# untitled.net
KiCad netlist of a schematic drawn in EAGLE
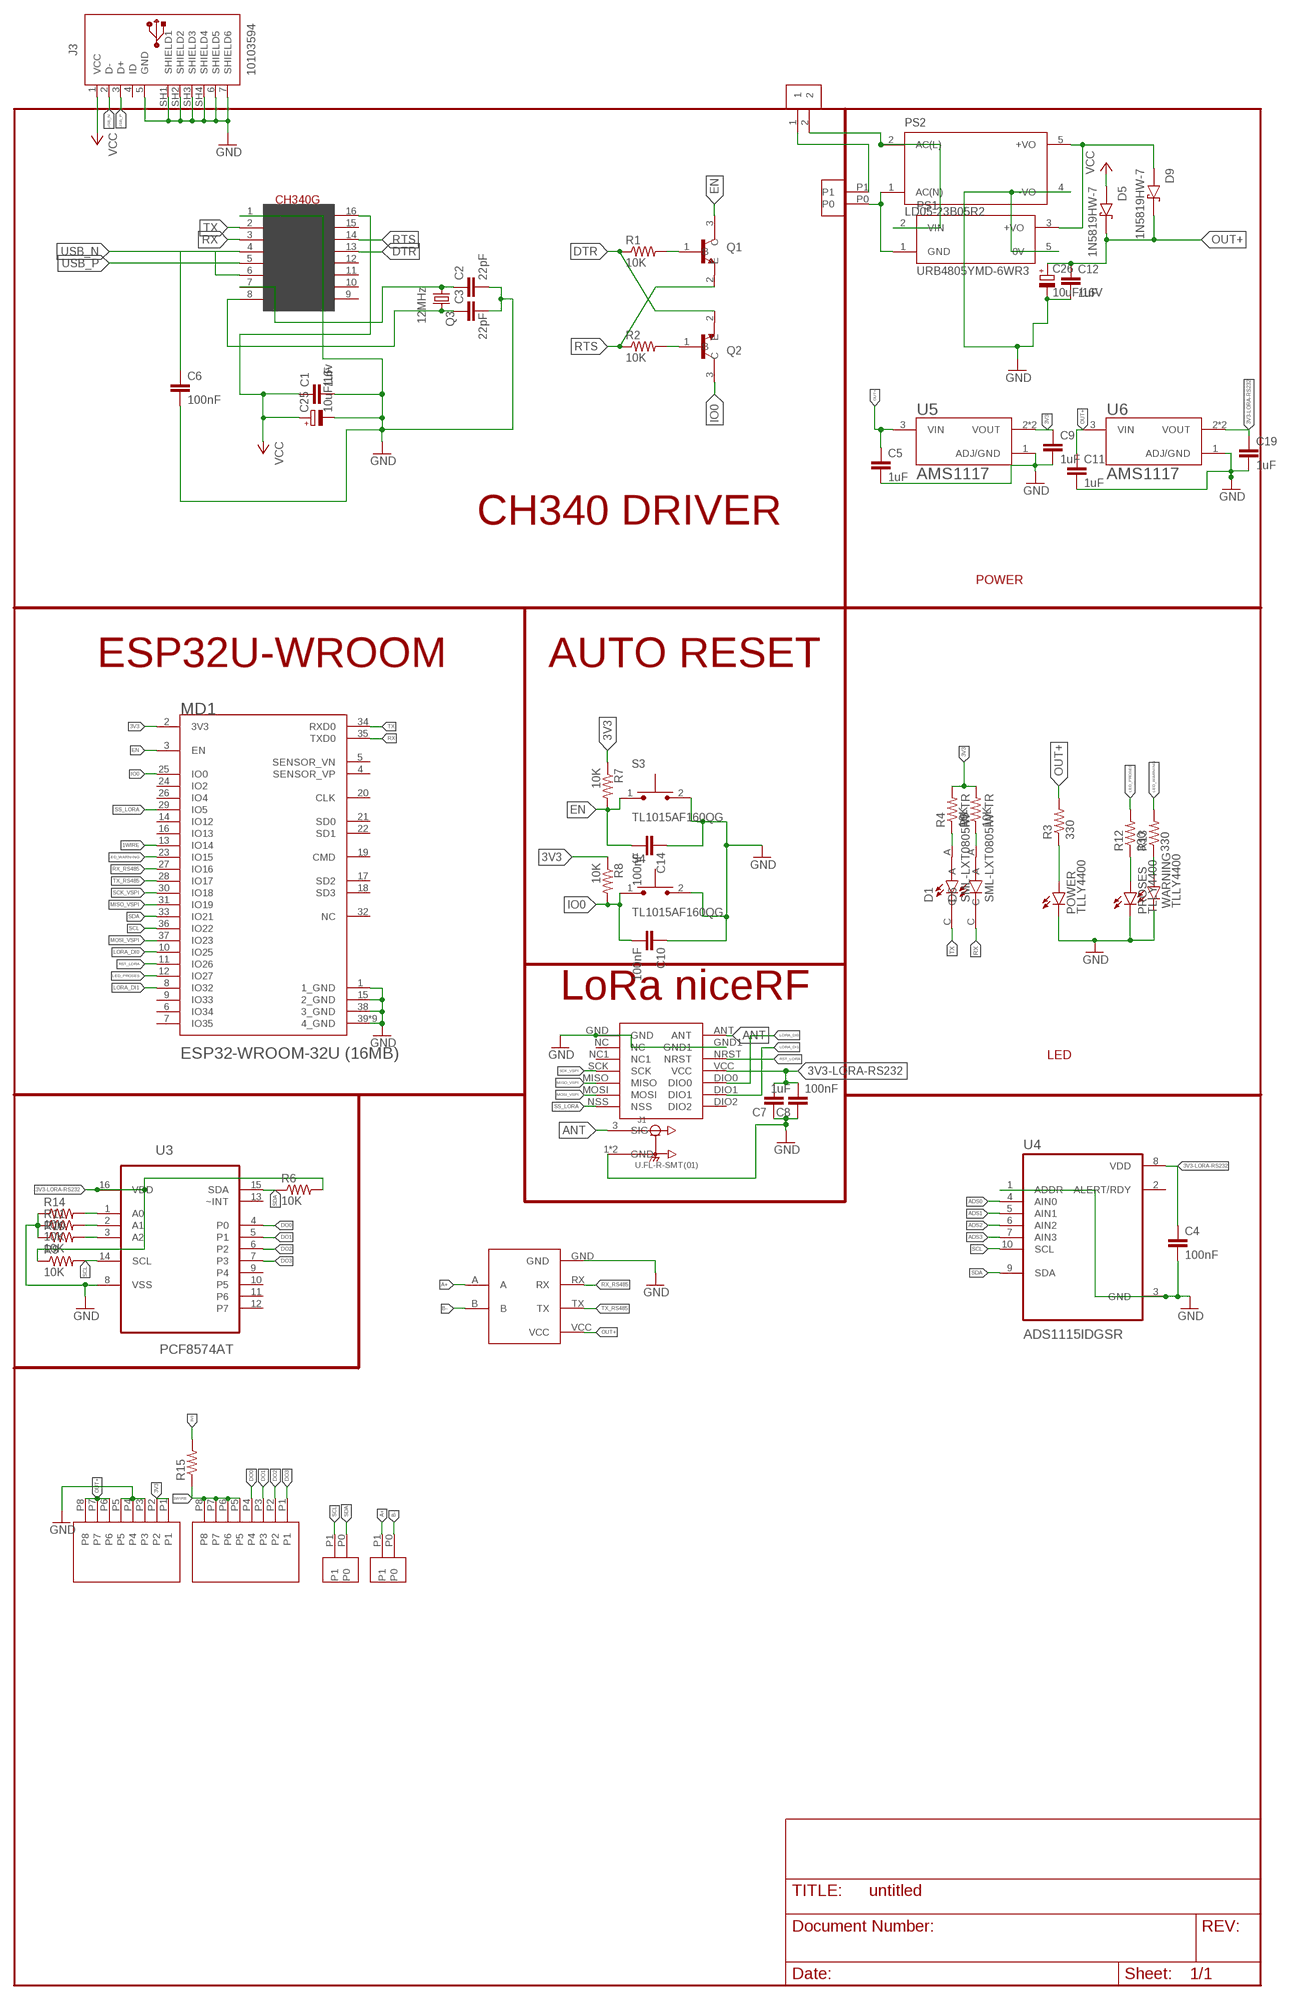
[diagram p0: schematic, sheet 1]

(export (version "E")
  (design (tool "Eeschema 10.0.6"))
  (components
    (comp (ref "C1")
      (value "1uF")
      (footprint "eagle-import:C0805K")
      (libsource (lib "eagle-import") (part "C-EUC0805K"))
    )
    (comp (ref "C2")
      (value "22pF")
      (footprint "eagle-import:C0805K")
      (libsource (lib "eagle-import") (part "C-EUC0805K"))
    )
    (comp (ref "C3")
      (value "22pF")
      (footprint "eagle-import:C0805K")
      (libsource (lib "eagle-import") (part "C-EUC0805K"))
    )
    (comp (ref "C4")
      (value "100nF")
      (footprint "eagle-import:C0805K")
      (libsource (lib "eagle-import") (part "C-EUC0805K"))
    )
    (comp (ref "C5")
      (value "1uF")
      (footprint "eagle-import:C0805K")
      (libsource (lib "eagle-import") (part "C-EUC0805K"))
    )
    (comp (ref "C6")
      (value "100nF")
      (footprint "eagle-import:C0805K")
      (libsource (lib "eagle-import") (part "C-EUC0805K"))
    )
    (comp (ref "C7")
      (value "1uF")
      (footprint "eagle-import:C0805K")
      (libsource (lib "eagle-import") (part "C-EUC0805K"))
    )
    (comp (ref "C8")
      (value "100nF")
      (footprint "eagle-import:C0805K")
      (libsource (lib "eagle-import") (part "C-EUC0805K"))
    )
    (comp (ref "C9")
      (value "1uF")
      (footprint "eagle-import:C0805K")
      (libsource (lib "eagle-import") (part "C-EUC0805K"))
    )
    (comp (ref "C10")
      (value "100nF")
      (footprint "eagle-import:C0805K")
      (libsource (lib "eagle-import") (part "C-EUC0805K"))
    )
    (comp (ref "C11")
      (value "1uF")
      (footprint "eagle-import:C0805K")
      (libsource (lib "eagle-import") (part "C-EUC0805K"))
    )
    (comp (ref "C12")
      (value "1uF")
      (footprint "eagle-import:C0805K")
      (libsource (lib "eagle-import") (part "C-EUC0805K"))
    )
    (comp (ref "C14")
      (value "100nF")
      (footprint "eagle-import:C0805K")
      (libsource (lib "eagle-import") (part "C-EUC0805K"))
    )
    (comp (ref "C19")
      (value "1uF")
      (footprint "eagle-import:C0805K")
      (libsource (lib "eagle-import") (part "C-EUC0805K"))
    )
    (comp (ref "C25")
      (value "10uF/16v")
      (footprint "eagle-import:153CLV-0505")
      (libsource (lib "eagle-import") (part "CPOL-EU153CLV-0505"))
    )
    (comp (ref "C26")
      (value "10uF/16V")
      (footprint "eagle-import:153CLV-0505")
      (libsource (lib "eagle-import") (part "CPOL-EU153CLV-0505"))
    )
    (comp (ref "CONN2P-3.5PI1")
      (value "CONN2P-3.5PI")
      (footprint "eagle-import:CONN2P-3.5PI")
      (libsource (lib "eagle-import") (part "CONN2P-3.5PI"))
    )
    (comp (ref "CONN2P-3.5PI2")
      (value "CONN2P-3.5PI")
      (footprint "eagle-import:CONN2P-3.5PI")
      (libsource (lib "eagle-import") (part "CONN2P-3.5PI"))
    )
    (comp (ref "CONN2P-3.5PI3")
      (value "CONN2P-3.5PI")
      (footprint "eagle-import:CONN2P-3.5PI")
      (libsource (lib "eagle-import") (part "CONN2P-3.5PI"))
    )
    (comp (ref "CONN3.1")
      (value "CONN3.5")
      (footprint "eagle-import:CONN3.5")
      (libsource (lib "eagle-import") (part "CONN3.5"))
    )
    (comp (ref "CONN3.2")
      (value "CONN3.5")
      (footprint "eagle-import:CONN3.5")
      (libsource (lib "eagle-import") (part "CONN3.5"))
    )
    (comp (ref "D1")
      (value "SML-LXT0805IW-TR")
      (footprint "eagle-import:LEDC2012X120N")
      (fields (field (name "MF") "Lumex Opto/Components"))
      (libsource (lib "eagle-import") (part "SML-LXT0805IW-TR"))
    )
    (comp (ref "D5")
      (value "1N5819HW-7")
      (footprint "eagle-import:SOD3715X145N")
      (fields (field (name "MF") "Diodes Inc."))
      (libsource (lib "eagle-import") (part "1N5819HW-7"))
    )
    (comp (ref "D6")
      (value "SML-LXT0805IW-TR")
      (footprint "eagle-import:LEDC2012X120N")
      (fields (field (name "MF") "Lumex Opto/Components"))
      (libsource (lib "eagle-import") (part "SML-LXT0805IW-TR"))
    )
    (comp (ref "D9")
      (value "1N5819HW-7")
      (footprint "eagle-import:SOD3715X145N")
      (fields (field (name "MF") "Diodes Inc."))
      (libsource (lib "eagle-import") (part "1N5819HW-7"))
    )
    (comp (ref "FUSE-KOTAK1")
      (value "FUSE-KOTAK")
      (footprint "eagle-import:FUSE-KOTAK")
      (libsource (lib "eagle-import") (part "FUSE-KOTAK"))
    )
    (comp (ref "J1")
      (value "U.FL-R-SMT(01)")
      (footprint "eagle-import:HRS_U.FL-R-SMT(01)")
      (fields (field (name "MF") "Hirose"))
      (libsource (lib "eagle-import") (part "U.FL-R-SMT(01)"))
    )
    (comp (ref "J3")
      (value "10103594")
      (footprint "eagle-import:10103594")
      (fields (field (name "MANUFACTURER") "Amphenol ICC (FCI)") (field (name "MPN") "10103594-0001LF"))
      (libsource (lib "eagle-import") (part "10103594"))
    )
    (comp (ref "LORA-NICERF-V1")
      (value "LORA-NICERF-V2")
      (footprint "eagle-import:LORA-NICERF-V2")
      (libsource (lib "eagle-import") (part "LORA-NICERF-V2"))
    )
    (comp (ref "MD1")
      (value "ESPRESSIF_SYSTEMS_ESP32-WROOM-32U_16MBESPRESSIF_SYSTEMS_ESP32-WROOM-32U_16MB_0_0")
      (footprint "eagle-import:ESPRESSIF_SYSTEMS_ESP32-WROOM-32U_16MB_0")
      (fields
        (field (name "DIGIKEY_PART_NUMBER") "1904-1028-1-ND")
        (field (name "MF") "Espressif Systems")
        (field (name "MOUSER_PART_NUMBER") "356-ES32WROOM32U16MB")
      )
      (libsource (lib "eagle-import") (part "ESPRESSIF_SYSTEMS_ESP32-WROOM-32U_16MBESPRESSIF_SYSTEMS_ESP32-WROOM-32U_16MB_0_0"))
    )
    (comp (ref "POWER")
      (value "TLLY4400")
      (footprint "eagle-import:LED3MM")
      (fields (field (name "MF") "VISHAY SEMICONDUCTOR"))
      (libsource (lib "eagle-import") (part "TLLY4400"))
    )
    (comp (ref "PROSES")
      (value "TLLY4400")
      (footprint "eagle-import:LED3MM")
      (fields (field (name "MF") "VISHAY SEMICONDUCTOR"))
      (libsource (lib "eagle-import") (part "TLLY4400"))
    )
    (comp (ref "PS1")
      (value "URB4805YMD-6WR3")
      (footprint "eagle-import:CONV_URB4805YMD-6WR3")
      (fields (field (name "MF") "Mornsun America, LLC"))
      (libsource (lib "eagle-import") (part "URB4805YMD-6WR3"))
    )
    (comp (ref "PS2")
      (value "LD05-23B05R2")
      (footprint "eagle-import:CONV_LD05-23B05R2")
      (fields (field (name "MF") "Mornsun America, LLC"))
      (libsource (lib "eagle-import") (part "LD05-23B05R2"))
    )
    (comp (ref "Q1")
      (value "MMBT3904")
      (footprint "eagle-import:SOT95P240X120-3N")
      (fields (field (name "MF") "STMicroelectronics"))
      (libsource (lib "eagle-import") (part "MMBT3904"))
    )
    (comp (ref "Q2")
      (value "MMBT3904")
      (footprint "eagle-import:SOT95P240X120-3N")
      (fields (field (name "MF") "STMicroelectronics"))
      (libsource (lib "eagle-import") (part "MMBT3904"))
    )
    (comp (ref "Q3")
      (value "12MHz")
      (footprint "eagle-import:SM49")
      (libsource (lib "eagle-import") (part "CRYSTALSM49"))
    )
    (comp (ref "R1")
      (value "10K")
      (footprint "eagle-import:M0805")
      (libsource (lib "eagle-import") (part "R-US_M0805"))
    )
    (comp (ref "R2")
      (value "10K")
      (footprint "eagle-import:M0805")
      (libsource (lib "eagle-import") (part "R-US_M0805"))
    )
    (comp (ref "R3")
      (value "330")
      (footprint "eagle-import:M0805")
      (libsource (lib "eagle-import") (part "R-US_M0805"))
    )
    (comp (ref "R4")
      (value "10K")
      (footprint "eagle-import:M0805")
      (libsource (lib "eagle-import") (part "R-US_M0805"))
    )
    (comp (ref "R5")
      (value "10K")
      (footprint "eagle-import:M0805")
      (libsource (lib "eagle-import") (part "R-US_M0805"))
    )
    (comp (ref "R6")
      (value "10K")
      (footprint "eagle-import:M0805")
      (libsource (lib "eagle-import") (part "R-US_M0805"))
    )
    (comp (ref "R7")
      (value "10K")
      (footprint "eagle-import:M0805")
      (libsource (lib "eagle-import") (part "R-US_M0805"))
    )
    (comp (ref "R8")
      (value "10K")
      (footprint "eagle-import:M0805")
      (libsource (lib "eagle-import") (part "R-US_M0805"))
    )
    (comp (ref "R9")
      (value "10K")
      (footprint "eagle-import:M0805")
      (libsource (lib "eagle-import") (part "R-US_M0805"))
    )
    (comp (ref "R10")
      (value "10K")
      (footprint "eagle-import:M0805")
      (libsource (lib "eagle-import") (part "R-US_M0805"))
    )
    (comp (ref "R11")
      (value "10K")
      (footprint "eagle-import:M0805")
      (libsource (lib "eagle-import") (part "R-US_M0805"))
    )
    (comp (ref "R12")
      (value "330")
      (footprint "eagle-import:M0805")
      (libsource (lib "eagle-import") (part "R-US_M0805"))
    )
    (comp (ref "R13")
      (value "330")
      (footprint "eagle-import:M0805")
      (libsource (lib "eagle-import") (part "R-US_M0805"))
    )
    (comp (ref "R14")
      (value "10K")
      (footprint "eagle-import:M0805")
      (libsource (lib "eagle-import") (part "R-US_M0805"))
    )
    (comp (ref "R15")
      (value "R-US_0207/10")
      (footprint "eagle-import:0207_10")
      (libsource (lib "eagle-import") (part "R-US_0207/10"))
    )
    (comp (ref "S3")
      (value "TL1015AF160QG")
      (footprint "eagle-import:SW_TL1015AF160QG")
      (fields (field (name "MF") "E-Switch"))
      (libsource (lib "eagle-import") (part "TL1015AF160QG"))
    )
    (comp (ref "S4")
      (value "TL1015AF160QG")
      (footprint "eagle-import:SW_TL1015AF160QG")
      (fields (field (name "MF") "E-Switch"))
      (libsource (lib "eagle-import") (part "TL1015AF160QG"))
    )
    (comp (ref "TTL-RS1")
      (value "TTL-RS485")
      (footprint "eagle-import:TTL-RS485")
      (libsource (lib "eagle-import") (part "TTL-RS485"))
    )
    (comp (ref "U$2")
      (value "CH340G")
      (footprint "eagle-import:SOIC16")
      (libsource (lib "eagle-import") (part "CH340G"))
    )
    (comp (ref "U3")
      (value "PCF8574AT")
      (footprint "eagle-import:SOIC127P1032X265-16N")
      (fields (field (name "MF") "NXP USA"))
      (libsource (lib "eagle-import") (part "PCF8574AT"))
    )
    (comp (ref "U4")
      (value "ADS1115IDGSR")
      (footprint "eagle-import:SOP50P490X110-10N")
      (fields (field (name "MF") "Texas Instruments"))
      (libsource (lib "eagle-import") (part "ADS1115IDGSR"))
    )
    (comp (ref "U5")
      (value "AMS1117")
      (footprint "eagle-import:SOT229P700X180-4N")
      (fields (field (name "MF") "Advanced Monolithic Systems"))
      (libsource (lib "eagle-import") (part "AMS1117"))
    )
    (comp (ref "U6")
      (value "AMS1117")
      (footprint "eagle-import:SOT229P700X180-4N")
      (fields (field (name "MF") "Advanced Monolithic Systems"))
      (libsource (lib "eagle-import") (part "AMS1117"))
    )
    (comp (ref "WARNING")
      (value "TLLY4400")
      (footprint "eagle-import:LED3MM")
      (fields (field (name "MF") "VISHAY SEMICONDUCTOR"))
      (libsource (lib "eagle-import") (part "TLLY4400"))
    )
  )
  (nets
    (net (code "1") (name "1WIRE") (class "Default")
      (node (ref "CONN3.2") (pin "P5") (pinfunction "P5_P5") (pintype "bidirectional"))
      (node (ref "CONN3.2") (pin "P6") (pinfunction "P6_P6") (pintype "bidirectional"))
      (node (ref "CONN3.2") (pin "P7") (pinfunction "P7_P7") (pintype "bidirectional"))
      (node (ref "CONN3.2") (pin "P8") (pinfunction "P8_P8") (pintype "bidirectional"))
      (node (ref "MD1") (pin "13") (pinfunction "IO14_13") (pintype "bidirectional"))
      (node (ref "R15") (pin "1") (pinfunction "1_1") (pintype "passive"))
    )
    (net (code "2") (name "3V3") (class "Default")
      (node (ref "C9") (pin "1") (pinfunction "1_1") (pintype "passive"))
      (node (ref "CONN3.1") (pin "P1") (pinfunction "P1_P1") (pintype "bidirectional"))
      (node (ref "CONN3.1") (pin "P2") (pinfunction "P2_P2") (pintype "bidirectional"))
      (node (ref "MD1") (pin "2") (pinfunction "3V3_2") (pintype "power_in"))
      (node (ref "R15") (pin "2") (pinfunction "2_2") (pintype "passive"))
      (node (ref "R4") (pin "2") (pinfunction "2_2") (pintype "passive"))
      (node (ref "R5") (pin "2") (pinfunction "2_2") (pintype "passive"))
      (node (ref "R7") (pin "1") (pinfunction "1_1") (pintype "passive"))
      (node (ref "R8") (pin "1") (pinfunction "1_1") (pintype "passive"))
      (node (ref "U5") (pin "2") (pinfunction "VOUT_2") (pintype "output"))
      (node (ref "U5") (pin "4") (pinfunction "VOUT_4") (pintype "output"))
    )
    (net (code "3") (name "3V3-LORA-RS232") (class "Default")
      (node (ref "C19") (pin "1") (pinfunction "1_1") (pintype "passive"))
      (node (ref "C4") (pin "1") (pinfunction "1_1") (pintype "passive"))
      (node (ref "C7") (pin "2") (pinfunction "2_2") (pintype "passive"))
      (node (ref "C8") (pin "2") (pinfunction "2_2") (pintype "passive"))
      (node (ref "LORA-NICERF-V1") (pin "VCC") (pinfunction "VCC_VCC") (pintype "bidirectional"))
      (node (ref "R6") (pin "2") (pinfunction "2_2") (pintype "passive"))
      (node (ref "R9") (pin "1") (pinfunction "1_1") (pintype "passive"))
      (node (ref "U3") (pin "16") (pinfunction "VDD_16") (pintype "power_in"))
      (node (ref "U4") (pin "8") (pinfunction "VDD_8") (pintype "power_in"))
      (node (ref "U6") (pin "2") (pinfunction "VOUT_2") (pintype "output"))
      (node (ref "U6") (pin "4") (pinfunction "VOUT_4") (pintype "output"))
    )
    (net (code "4") (name "A+") (class "Default")
      (node (ref "CONN2P-3.5PI3") (pin "P1") (pinfunction "P1_P1") (pintype "bidirectional"))
      (node (ref "TTL-RS1") (pin "A") (pinfunction "A_A") (pintype "bidirectional"))
    )
    (net (code "5") (name "ADS0") (class "Default")
      (node (ref "U4") (pin "4") (pinfunction "AIN0_4") (pintype "input"))
    )
    (net (code "6") (name "ADS1") (class "Default")
      (node (ref "U4") (pin "5") (pinfunction "AIN1_5") (pintype "input"))
    )
    (net (code "7") (name "ADS2") (class "Default")
      (node (ref "U4") (pin "6") (pinfunction "AIN2_6") (pintype "input"))
    )
    (net (code "8") (name "ADS3") (class "Default")
      (node (ref "U4") (pin "7") (pinfunction "AIN3_7") (pintype "input"))
    )
    (net (code "9") (name "ANT") (class "Default")
      (node (ref "J1") (pin "3") (pinfunction "SIG_3") (pintype "passive"))
      (node (ref "LORA-NICERF-V1") (pin "ANT") (pinfunction "ANT_ANT") (pintype "bidirectional"))
    )
    (net (code "10") (name "B-") (class "Default")
      (node (ref "CONN2P-3.5PI3") (pin "P0") (pinfunction "P0_P0") (pintype "bidirectional"))
      (node (ref "TTL-RS1") (pin "B") (pinfunction "B_B") (pintype "bidirectional"))
    )
    (net (code "11") (name "DO0") (class "Default")
      (node (ref "CONN3.2") (pin "P4") (pinfunction "P4_P4") (pintype "bidirectional"))
      (node (ref "U3") (pin "4") (pinfunction "P0_4") (pintype "bidirectional"))
    )
    (net (code "12") (name "DO1") (class "Default")
      (node (ref "CONN3.2") (pin "P3") (pinfunction "P3_P3") (pintype "bidirectional"))
      (node (ref "U3") (pin "5") (pinfunction "P1_5") (pintype "bidirectional"))
    )
    (net (code "13") (name "DO2") (class "Default")
      (node (ref "CONN3.2") (pin "P2") (pinfunction "P2_P2") (pintype "bidirectional"))
      (node (ref "U3") (pin "6") (pinfunction "P2_6") (pintype "bidirectional"))
    )
    (net (code "14") (name "DO3") (class "Default")
      (node (ref "CONN3.2") (pin "P1") (pinfunction "P1_P1") (pintype "bidirectional"))
      (node (ref "U3") (pin "7") (pinfunction "P3_7") (pintype "bidirectional"))
    )
    (net (code "15") (name "DTR") (class "Default")
      (node (ref "Q2") (pin "2") (pinfunction "E_2") (pintype "passive"))
      (node (ref "R1") (pin "1") (pinfunction "1_1") (pintype "passive"))
      (node (ref "U$2") (pin "13") (pinfunction "DTR_13") (pintype "bidirectional"))
    )
    (net (code "16") (name "EN") (class "Default")
      (node (ref "C14") (pin "2") (pinfunction "2_2") (pintype "passive"))
      (node (ref "MD1") (pin "3") (pinfunction "EN_3") (pintype "input"))
      (node (ref "Q1") (pin "3") (pinfunction "C_3") (pintype "passive"))
      (node (ref "R7") (pin "2") (pinfunction "2_2") (pintype "passive"))
      (node (ref "S3") (pin "1") (pinfunction "1_1") (pintype "passive"))
    )
    (net (code "17") (name "GND") (class "Default")
      (node (ref "C1") (pin "2") (pinfunction "2_2") (pintype "passive"))
      (node (ref "C10") (pin "1") (pinfunction "1_1") (pintype "passive"))
      (node (ref "C11") (pin "2") (pinfunction "2_2") (pintype "passive"))
      (node (ref "C12") (pin "2") (pinfunction "2_2") (pintype "passive"))
      (node (ref "C14") (pin "1") (pinfunction "1_1") (pintype "passive"))
      (node (ref "C19") (pin "2") (pinfunction "2_2") (pintype "passive"))
      (node (ref "C2") (pin "2") (pinfunction "2_2") (pintype "passive"))
      (node (ref "C25") (pin "-") (pinfunction "-_-") (pintype "passive"))
      (node (ref "C26") (pin "-") (pinfunction "-_-") (pintype "passive"))
      (node (ref "C3") (pin "2") (pinfunction "2_2") (pintype "passive"))
      (node (ref "C4") (pin "2") (pinfunction "2_2") (pintype "passive"))
      (node (ref "C5") (pin "2") (pinfunction "2_2") (pintype "passive"))
      (node (ref "C6") (pin "2") (pinfunction "2_2") (pintype "passive"))
      (node (ref "C7") (pin "1") (pinfunction "1_1") (pintype "passive"))
      (node (ref "C8") (pin "1") (pinfunction "1_1") (pintype "passive"))
      (node (ref "C9") (pin "2") (pinfunction "2_2") (pintype "passive"))
      (node (ref "CONN3.1") (pin "P3") (pinfunction "P3_P3") (pintype "bidirectional"))
      (node (ref "CONN3.1") (pin "P4") (pinfunction "P4_P4") (pintype "bidirectional"))
      (node (ref "CONN3.1") (pin "P5") (pinfunction "P5_P5") (pintype "bidirectional"))
      (node (ref "J1") (pin "1") (pinfunction "GND_1") (pintype "passive"))
      (node (ref "J1") (pin "2") (pinfunction "GND_2") (pintype "passive"))
      (node (ref "J3") (pin "5") (pinfunction "GND_5") (pintype "power_in"))
      (node (ref "J3") (pin "6") (pinfunction "SHIELD5_6") (pintype "power_in"))
      (node (ref "J3") (pin "7") (pinfunction "SHIELD6_7") (pintype "power_in"))
      (node (ref "J3") (pin "SH1") (pinfunction "SHIELD1_SH1") (pintype "power_in"))
      (node (ref "J3") (pin "SH2") (pinfunction "SHIELD2_SH2") (pintype "power_in"))
      (node (ref "J3") (pin "SH3") (pinfunction "SHIELD3_SH3") (pintype "power_in"))
      (node (ref "J3") (pin "SH4") (pinfunction "SHIELD4_SH4") (pintype "power_in"))
      (node (ref "LORA-NICERF-V1") (pin "GND") (pinfunction "GND_GND") (pintype "bidirectional"))
      (node (ref "LORA-NICERF-V1") (pin "GND1") (pinfunction "GND1_GND1") (pintype "bidirectional"))
      (node (ref "MD1") (pin "1") (pinfunction "1_GND_1") (pintype "power_in"))
      (node (ref "MD1") (pin "15") (pinfunction "2_GND_15") (pintype "power_in"))
      (node (ref "MD1") (pin "38") (pinfunction "3_GND_38") (pintype "power_in"))
      (node (ref "MD1") (pin "39") (pinfunction "4_GND_39") (pintype "power_in"))
      (node (ref "MD1") (pin "39-2") (pinfunction "4_GND_39-2") (pintype "power_in"))
      (node (ref "MD1") (pin "39-3") (pinfunction "4_GND_39-3") (pintype "power_in"))
      (node (ref "MD1") (pin "39-4") (pinfunction "4_GND_39-4") (pintype "power_in"))
      (node (ref "MD1") (pin "39-5") (pinfunction "4_GND_39-5") (pintype "power_in"))
      (node (ref "MD1") (pin "39-6") (pinfunction "4_GND_39-6") (pintype "power_in"))
      (node (ref "MD1") (pin "39-7") (pinfunction "4_GND_39-7") (pintype "power_in"))
      (node (ref "MD1") (pin "39-8") (pinfunction "4_GND_39-8") (pintype "power_in"))
      (node (ref "MD1") (pin "39-9") (pinfunction "4_GND_39-9") (pintype "power_in"))
      (node (ref "POWER") (pin "K") (pinfunction "C_K") (pintype "passive"))
      (node (ref "PROSES") (pin "K") (pinfunction "C_K") (pintype "passive"))
      (node (ref "PS1") (pin "5") (pinfunction "0V_5") (pintype "passive"))
      (node (ref "PS2") (pin "4") (pinfunction "-VO_4") (pintype "output"))
      (node (ref "R10") (pin "1") (pinfunction "1_1") (pintype "passive"))
      (node (ref "R11") (pin "1") (pinfunction "1_1") (pintype "passive"))
      (node (ref "R14") (pin "1") (pinfunction "1_1") (pintype "passive"))
      (node (ref "S3") (pin "2") (pinfunction "2_2") (pintype "passive"))
      (node (ref "S4") (pin "2") (pinfunction "2_2") (pintype "passive"))
      (node (ref "TTL-RS1") (pin "GND") (pinfunction "GND_GND") (pintype "bidirectional"))
      (node (ref "U$2") (pin "1") (pinfunction "GND_1") (pintype "bidirectional"))
      (node (ref "U3") (pin "8") (pinfunction "VSS_8") (pintype "passive"))
      (node (ref "U4") (pin "1") (pinfunction "ADDR_1") (pintype "input"))
      (node (ref "U4") (pin "3") (pinfunction "GND_3") (pintype "power_in"))
      (node (ref "U5") (pin "1") (pinfunction "ADJ/GND_1") (pintype "power_in"))
      (node (ref "U6") (pin "1") (pinfunction "ADJ/GND_1") (pintype "power_in"))
      (node (ref "WARNING") (pin "K") (pinfunction "C_K") (pintype "passive"))
    )
    (net (code "18") (name "IO0") (class "Default")
      (node (ref "C10") (pin "2") (pinfunction "2_2") (pintype "passive"))
      (node (ref "MD1") (pin "25") (pinfunction "IO0_25") (pintype "bidirectional"))
      (node (ref "Q2") (pin "3") (pinfunction "C_3") (pintype "passive"))
      (node (ref "R8") (pin "2") (pinfunction "2_2") (pintype "passive"))
      (node (ref "S4") (pin "1") (pinfunction "1_1") (pintype "passive"))
    )
    (net (code "19") (name "LED_PROSES") (class "Default")
      (node (ref "MD1") (pin "12") (pinfunction "IO27_12") (pintype "bidirectional"))
      (node (ref "R12") (pin "2") (pinfunction "2_2") (pintype "passive"))
    )
    (net (code "20") (name "LED_WARNING") (class "Default")
      (node (ref "MD1") (pin "23") (pinfunction "IO15_23") (pintype "bidirectional"))
      (node (ref "R13") (pin "2") (pinfunction "2_2") (pintype "passive"))
    )
    (net (code "21") (name "LORA_DI0") (class "Default")
      (node (ref "LORA-NICERF-V1") (pin "DIO0") (pinfunction "DIO0_DIO0") (pintype "bidirectional"))
      (node (ref "MD1") (pin "10") (pinfunction "IO25_10") (pintype "bidirectional"))
    )
    (net (code "22") (name "LORA_DI1") (class "Default")
      (node (ref "LORA-NICERF-V1") (pin "DIO1") (pinfunction "DIO1_DIO1") (pintype "bidirectional"))
      (node (ref "MD1") (pin "8") (pinfunction "IO32_8") (pintype "bidirectional"))
    )
    (net (code "23") (name "MISO_VSPI") (class "Default")
      (node (ref "LORA-NICERF-V1") (pin "MISO") (pinfunction "MISO_MISO") (pintype "bidirectional"))
      (node (ref "MD1") (pin "31") (pinfunction "IO19_31") (pintype "bidirectional"))
    )
    (net (code "24") (name "MOSI_VSPI") (class "Default")
      (node (ref "LORA-NICERF-V1") (pin "MOSI") (pinfunction "MOSI_MOSI") (pintype "bidirectional"))
      (node (ref "MD1") (pin "37") (pinfunction "IO23_37") (pintype "bidirectional"))
    )
    (net (code "25") (name "Net-(CONN2P-3.5PI1-PadP1)") (class "Default")
      (node (ref "CONN2P-3.5PI1") (pin "P1") (pinfunction "P1_P1") (pintype "bidirectional"))
      (node (ref "FUSE-KOTAK1") (pin "1") (pinfunction "1_1") (pintype "bidirectional"))
    )
    (net (code "26") (name "Net-(D1-PadA)") (class "Default")
      (node (ref "D1") (pin "A") (pinfunction "A_A") (pintype "passive"))
      (node (ref "R4") (pin "1") (pinfunction "1_1") (pintype "passive"))
    )
    (net (code "27") (name "Net-(D6-PadA)") (class "Default")
      (node (ref "D6") (pin "A") (pinfunction "A_A") (pintype "passive"))
      (node (ref "R5") (pin "1") (pinfunction "1_1") (pintype "passive"))
    )
    (net (code "28") (name "Net-(POWER-PadA)") (class "Default")
      (node (ref "POWER") (pin "A") (pinfunction "A_A") (pintype "passive"))
      (node (ref "R3") (pin "1") (pinfunction "1_1") (pintype "passive"))
    )
    (net (code "29") (name "Net-(PROSES-PadA)") (class "Default")
      (node (ref "PROSES") (pin "A") (pinfunction "A_A") (pintype "passive"))
      (node (ref "R12") (pin "1") (pinfunction "1_1") (pintype "passive"))
    )
    (net (code "30") (name "Net-(PS1-+VO)") (class "Default")
      (node (ref "D9") (pin "A") (pinfunction "A_A") (pintype "passive"))
      (node (ref "PS1") (pin "3") (pinfunction "+VO_3") (pintype "output"))
      (node (ref "PS2") (pin "5") (pinfunction "+VO_5") (pintype "output"))
    )
    (net (code "31") (name "Net-(PS1-GND)") (class "Default")
      (node (ref "CONN2P-3.5PI1") (pin "P0") (pinfunction "P0_P0") (pintype "bidirectional"))
      (node (ref "PS1") (pin "1") (pinfunction "GND_1") (pintype "power_in"))
      (node (ref "PS2") (pin "1") (pinfunction "AC(N)_1") (pintype "input"))
    )
    (net (code "32") (name "Net-(PS1-VIN)") (class "Default")
      (node (ref "FUSE-KOTAK1") (pin "2") (pinfunction "2_2") (pintype "bidirectional"))
      (node (ref "PS1") (pin "2") (pinfunction "VIN_2") (pintype "input"))
      (node (ref "PS2") (pin "2") (pinfunction "AC(L)_2") (pintype "input"))
    )
    (net (code "33") (name "Net-(Q1-B)") (class "Default")
      (node (ref "Q1") (pin "1") (pinfunction "B_1") (pintype "passive"))
      (node (ref "R1") (pin "2") (pinfunction "2_2") (pintype "passive"))
    )
    (net (code "34") (name "Net-(Q2-B)") (class "Default")
      (node (ref "Q2") (pin "1") (pinfunction "B_1") (pintype "passive"))
      (node (ref "R2") (pin "2") (pinfunction "2_2") (pintype "passive"))
    )
    (net (code "35") (name "Net-(R13-Pad1)") (class "Default")
      (node (ref "R13") (pin "1") (pinfunction "1_1") (pintype "passive"))
      (node (ref "WARNING") (pin "A") (pinfunction "A_A") (pintype "passive"))
    )
    (net (code "36") (name "Net-(U$2-V3)") (class "Default")
      (node (ref "C6") (pin "1") (pinfunction "1_1") (pintype "passive"))
      (node (ref "U$2") (pin "4") (pinfunction "V3_4") (pintype "bidirectional"))
    )
    (net (code "37") (name "Net-(U$2-XI)") (class "Default")
      (node (ref "C2") (pin "1") (pinfunction "1_1") (pintype "passive"))
      (node (ref "Q3") (pin "1") (pinfunction "1_1") (pintype "passive"))
      (node (ref "U$2") (pin "7") (pinfunction "XI_7") (pintype "bidirectional"))
    )
    (net (code "38") (name "Net-(U$2-XO)") (class "Default")
      (node (ref "C3") (pin "1") (pinfunction "1_1") (pintype "passive"))
      (node (ref "Q3") (pin "2") (pinfunction "2_2") (pintype "passive"))
      (node (ref "U$2") (pin "8") (pinfunction "XO_8") (pintype "bidirectional"))
    )
    (net (code "39") (name "Net-(U3-A0)") (class "Default")
      (node (ref "R14") (pin "2") (pinfunction "2_2") (pintype "passive"))
      (node (ref "U3") (pin "1") (pinfunction "A0_1") (pintype "input"))
    )
    (net (code "40") (name "Net-(U3-A1)") (class "Default")
      (node (ref "R11") (pin "2") (pinfunction "2_2") (pintype "passive"))
      (node (ref "U3") (pin "2") (pinfunction "A1_2") (pintype "input"))
    )
    (net (code "41") (name "Net-(U3-A2)") (class "Default")
      (node (ref "R10") (pin "2") (pinfunction "2_2") (pintype "passive"))
      (node (ref "U3") (pin "3") (pinfunction "A2_3") (pintype "input"))
    )
    (net (code "42") (name "OUT+") (class "Default")
      (node (ref "C11") (pin "1") (pinfunction "1_1") (pintype "passive"))
      (node (ref "C12") (pin "1") (pinfunction "1_1") (pintype "passive"))
      (node (ref "C26") (pin "+") (pinfunction "+_+") (pintype "passive"))
      (node (ref "C5") (pin "1") (pinfunction "1_1") (pintype "passive"))
      (node (ref "CONN3.1") (pin "P6") (pinfunction "P6_P6") (pintype "bidirectional"))
      (node (ref "CONN3.1") (pin "P7") (pinfunction "P7_P7") (pintype "bidirectional"))
      (node (ref "CONN3.1") (pin "P8") (pinfunction "P8_P8") (pintype "bidirectional"))
      (node (ref "D5") (pin "C") (pinfunction "K_C") (pintype "passive"))
      (node (ref "D9") (pin "C") (pinfunction "K_C") (pintype "passive"))
      (node (ref "R3") (pin "2") (pinfunction "2_2") (pintype "passive"))
      (node (ref "TTL-RS1") (pin "VCC") (pinfunction "VCC_VCC") (pintype "bidirectional"))
      (node (ref "U5") (pin "3") (pinfunction "VIN_3") (pintype "input"))
      (node (ref "U6") (pin "3") (pinfunction "VIN_3") (pintype "input"))
    )
    (net (code "43") (name "RST_LORA") (class "Default")
      (node (ref "LORA-NICERF-V1") (pin "NRST") (pinfunction "NRST_NRST") (pintype "bidirectional"))
      (node (ref "MD1") (pin "11") (pinfunction "IO26_11") (pintype "bidirectional"))
    )
    (net (code "44") (name "RTS") (class "Default")
      (node (ref "Q1") (pin "2") (pinfunction "E_2") (pintype "passive"))
      (node (ref "R2") (pin "1") (pinfunction "1_1") (pintype "passive"))
      (node (ref "U$2") (pin "14") (pinfunction "RTS_14") (pintype "bidirectional"))
    )
    (net (code "45") (name "RX") (class "Default")
      (node (ref "D6") (pin "C") (pinfunction "C_C") (pintype "passive"))
      (node (ref "MD1") (pin "35") (pinfunction "TXD0_35") (pintype "bidirectional"))
      (node (ref "U$2") (pin "3") (pinfunction "RX_3") (pintype "bidirectional"))
    )
    (net (code "46") (name "RX_RS485") (class "Default")
      (node (ref "MD1") (pin "27") (pinfunction "IO16_27") (pintype "bidirectional"))
      (node (ref "TTL-RS1") (pin "RX") (pinfunction "RX_RX") (pintype "bidirectional"))
    )
    (net (code "47") (name "SCK_VSPI") (class "Default")
      (node (ref "LORA-NICERF-V1") (pin "SCK") (pinfunction "SCK_SCK") (pintype "bidirectional"))
      (node (ref "MD1") (pin "30") (pinfunction "IO18_30") (pintype "bidirectional"))
    )
    (net (code "48") (name "SCL") (class "Default")
      (node (ref "CONN2P-3.5PI2") (pin "P1") (pinfunction "P1_P1") (pintype "bidirectional"))
      (node (ref "MD1") (pin "36") (pinfunction "IO22_36") (pintype "bidirectional"))
      (node (ref "R9") (pin "2") (pinfunction "2_2") (pintype "passive"))
      (node (ref "U3") (pin "14") (pinfunction "SCL_14") (pintype "input"))
      (node (ref "U4") (pin "10") (pinfunction "SCL_10") (pintype "input"))
    )
    (net (code "49") (name "SDA") (class "Default")
      (node (ref "CONN2P-3.5PI2") (pin "P0") (pinfunction "P0_P0") (pintype "bidirectional"))
      (node (ref "MD1") (pin "33") (pinfunction "IO21_33") (pintype "bidirectional"))
      (node (ref "R6") (pin "1") (pinfunction "1_1") (pintype "passive"))
      (node (ref "U3") (pin "15") (pinfunction "SDA_15") (pintype "bidirectional"))
      (node (ref "U4") (pin "9") (pinfunction "SDA_9") (pintype "bidirectional"))
    )
    (net (code "50") (name "SS_LORA") (class "Default")
      (node (ref "LORA-NICERF-V1") (pin "NSS") (pinfunction "NSS_NSS") (pintype "bidirectional"))
      (node (ref "MD1") (pin "29") (pinfunction "IO5_29") (pintype "bidirectional"))
    )
    (net (code "51") (name "TX") (class "Default")
      (node (ref "D1") (pin "C") (pinfunction "C_C") (pintype "passive"))
      (node (ref "MD1") (pin "34") (pinfunction "RXD0_34") (pintype "bidirectional"))
      (node (ref "U$2") (pin "2") (pinfunction "TX_2") (pintype "bidirectional"))
    )
    (net (code "52") (name "TX_RS485") (class "Default")
      (node (ref "MD1") (pin "28") (pinfunction "IO17_28") (pintype "bidirectional"))
      (node (ref "TTL-RS1") (pin "TX") (pinfunction "TX_TX") (pintype "bidirectional"))
    )
    (net (code "53") (name "USB_N") (class "Default")
      (node (ref "J3") (pin "2") (pinfunction "D-_2") (pintype "bidirectional"))
      (node (ref "U$2") (pin "6") (pinfunction "D-_6") (pintype "bidirectional"))
    )
    (net (code "54") (name "USB_P") (class "Default")
      (node (ref "J3") (pin "3") (pinfunction "D+_3") (pintype "bidirectional"))
      (node (ref "U$2") (pin "5") (pinfunction "D+_5") (pintype "bidirectional"))
    )
    (net (code "55") (name "VCC") (class "Default")
      (node (ref "C1") (pin "1") (pinfunction "1_1") (pintype "passive"))
      (node (ref "C25") (pin "+") (pinfunction "+_+") (pintype "passive"))
      (node (ref "D5") (pin "A") (pinfunction "A_A") (pintype "passive"))
      (node (ref "J3") (pin "1") (pinfunction "VCC_1") (pintype "power_in"))
      (node (ref "U$2") (pin "16") (pinfunction "VCC_16") (pintype "bidirectional"))
    )
    (net (code "56") (name "unconnected-(J3-ID-Pad4)") (class "Default")
      (node (ref "J3") (pin "4") (pinfunction "ID_4") (pintype "bidirectional"))
    )
    (net (code "57") (name "unconnected-(LORA-NICERF-V1-PadDIO2)") (class "Default")
      (node (ref "LORA-NICERF-V1") (pin "DIO2") (pinfunction "DIO2_DIO2") (pintype "bidirectional"))
    )
    (net (code "58") (name "unconnected-(LORA-NICERF-V1-PadNC)") (class "Default")
      (node (ref "LORA-NICERF-V1") (pin "NC") (pinfunction "NC_NC") (pintype "bidirectional"))
    )
    (net (code "59") (name "unconnected-(LORA-NICERF-V1-PadNC1)") (class "Default")
      (node (ref "LORA-NICERF-V1") (pin "NC1") (pinfunction "NC1_NC1") (pintype "bidirectional"))
    )
    (net (code "60") (name "unconnected-(MD1-CLK-Pad20)") (class "Default")
      (node (ref "MD1") (pin "20") (pinfunction "CLK_20") (pintype "bidirectional"))
    )
    (net (code "61") (name "unconnected-(MD1-CMD-Pad19)") (class "Default")
      (node (ref "MD1") (pin "19") (pinfunction "CMD_19") (pintype "bidirectional"))
    )
    (net (code "62") (name "unconnected-(MD1-IO2-Pad24)") (class "Default")
      (node (ref "MD1") (pin "24") (pinfunction "IO2_24") (pintype "bidirectional"))
    )
    (net (code "63") (name "unconnected-(MD1-IO4-Pad26)") (class "Default")
      (node (ref "MD1") (pin "26") (pinfunction "IO4_26") (pintype "bidirectional"))
    )
    (net (code "64") (name "unconnected-(MD1-IO12-Pad14)") (class "Default")
      (node (ref "MD1") (pin "14") (pinfunction "IO12_14") (pintype "bidirectional"))
    )
    (net (code "65") (name "unconnected-(MD1-IO13-Pad16)") (class "Default")
      (node (ref "MD1") (pin "16") (pinfunction "IO13_16") (pintype "bidirectional"))
    )
    (net (code "66") (name "unconnected-(MD1-IO33-Pad9)") (class "Default")
      (node (ref "MD1") (pin "9") (pinfunction "IO33_9") (pintype "bidirectional"))
    )
    (net (code "67") (name "unconnected-(MD1-IO34-Pad6)") (class "Default")
      (node (ref "MD1") (pin "6") (pinfunction "IO34_6") (pintype "bidirectional"))
    )
    (net (code "68") (name "unconnected-(MD1-IO35-Pad7)") (class "Default")
      (node (ref "MD1") (pin "7") (pinfunction "IO35_7") (pintype "bidirectional"))
    )
    (net (code "69") (name "unconnected-(MD1-NC-Pad32)") (class "Default")
      (node (ref "MD1") (pin "32") (pinfunction "NC_32") (pintype "passive"))
    )
    (net (code "70") (name "unconnected-(MD1-SD0-Pad21)") (class "Default")
      (node (ref "MD1") (pin "21") (pinfunction "SD0_21") (pintype "bidirectional"))
    )
    (net (code "71") (name "unconnected-(MD1-SD1-Pad22)") (class "Default")
      (node (ref "MD1") (pin "22") (pinfunction "SD1_22") (pintype "bidirectional"))
    )
    (net (code "72") (name "unconnected-(MD1-SD2-Pad17)") (class "Default")
      (node (ref "MD1") (pin "17") (pinfunction "SD2_17") (pintype "bidirectional"))
    )
    (net (code "73") (name "unconnected-(MD1-SD3-Pad18)") (class "Default")
      (node (ref "MD1") (pin "18") (pinfunction "SD3_18") (pintype "bidirectional"))
    )
    (net (code "74") (name "unconnected-(MD1-SENSOR_VN-Pad5)") (class "Default")
      (node (ref "MD1") (pin "5") (pinfunction "SENSOR_VN_5") (pintype "input"))
    )
    (net (code "75") (name "unconnected-(MD1-SENSOR_VP-Pad4)") (class "Default")
      (node (ref "MD1") (pin "4") (pinfunction "SENSOR_VP_4") (pintype "input"))
    )
    (net (code "76") (name "unconnected-(U$2-CTS-Pad9)") (class "Default")
      (node (ref "U$2") (pin "9") (pinfunction "CTS_9") (pintype "bidirectional"))
    )
    (net (code "77") (name "unconnected-(U$2-DCD-Pad12)") (class "Default")
      (node (ref "U$2") (pin "12") (pinfunction "DCD_12") (pintype "bidirectional"))
    )
    (net (code "78") (name "unconnected-(U$2-DSR-Pad10)") (class "Default")
      (node (ref "U$2") (pin "10") (pinfunction "DSR_10") (pintype "bidirectional"))
    )
    (net (code "79") (name "unconnected-(U$2-RI-Pad11)") (class "Default")
      (node (ref "U$2") (pin "11") (pinfunction "RI_11") (pintype "bidirectional"))
    )
    (net (code "80") (name "unconnected-(U$2-RS232-Pad15)") (class "Default")
      (node (ref "U$2") (pin "15") (pinfunction "RS232_15") (pintype "bidirectional"))
    )
    (net (code "81") (name "unconnected-(U3-P4-Pad9)") (class "Default")
      (node (ref "U3") (pin "9") (pinfunction "P4_9") (pintype "bidirectional"))
    )
    (net (code "82") (name "unconnected-(U3-P5-Pad10)") (class "Default")
      (node (ref "U3") (pin "10") (pinfunction "P5_10") (pintype "bidirectional"))
    )
    (net (code "83") (name "unconnected-(U3-P6-Pad11)") (class "Default")
      (node (ref "U3") (pin "11") (pinfunction "P6_11") (pintype "bidirectional"))
    )
    (net (code "84") (name "unconnected-(U3-P7-Pad12)") (class "Default")
      (node (ref "U3") (pin "12") (pinfunction "P7_12") (pintype "bidirectional"))
    )
    (net (code "85") (name "unconnected-(U3-~{INT}-Pad13)") (class "Default")
      (node (ref "U3") (pin "13") (pinfunction "~{INT}_13") (pintype "output"))
    )
    (net (code "86") (name "unconnected-(U4-ALERT{slash}RDY-Pad2)") (class "Default")
      (node (ref "U4") (pin "2") (pinfunction "ALERT/RDY_2") (pintype "output"))
    )
  )
)
